# p-stop_03.net
KiCad netlist of a schematic drawn in EAGLE
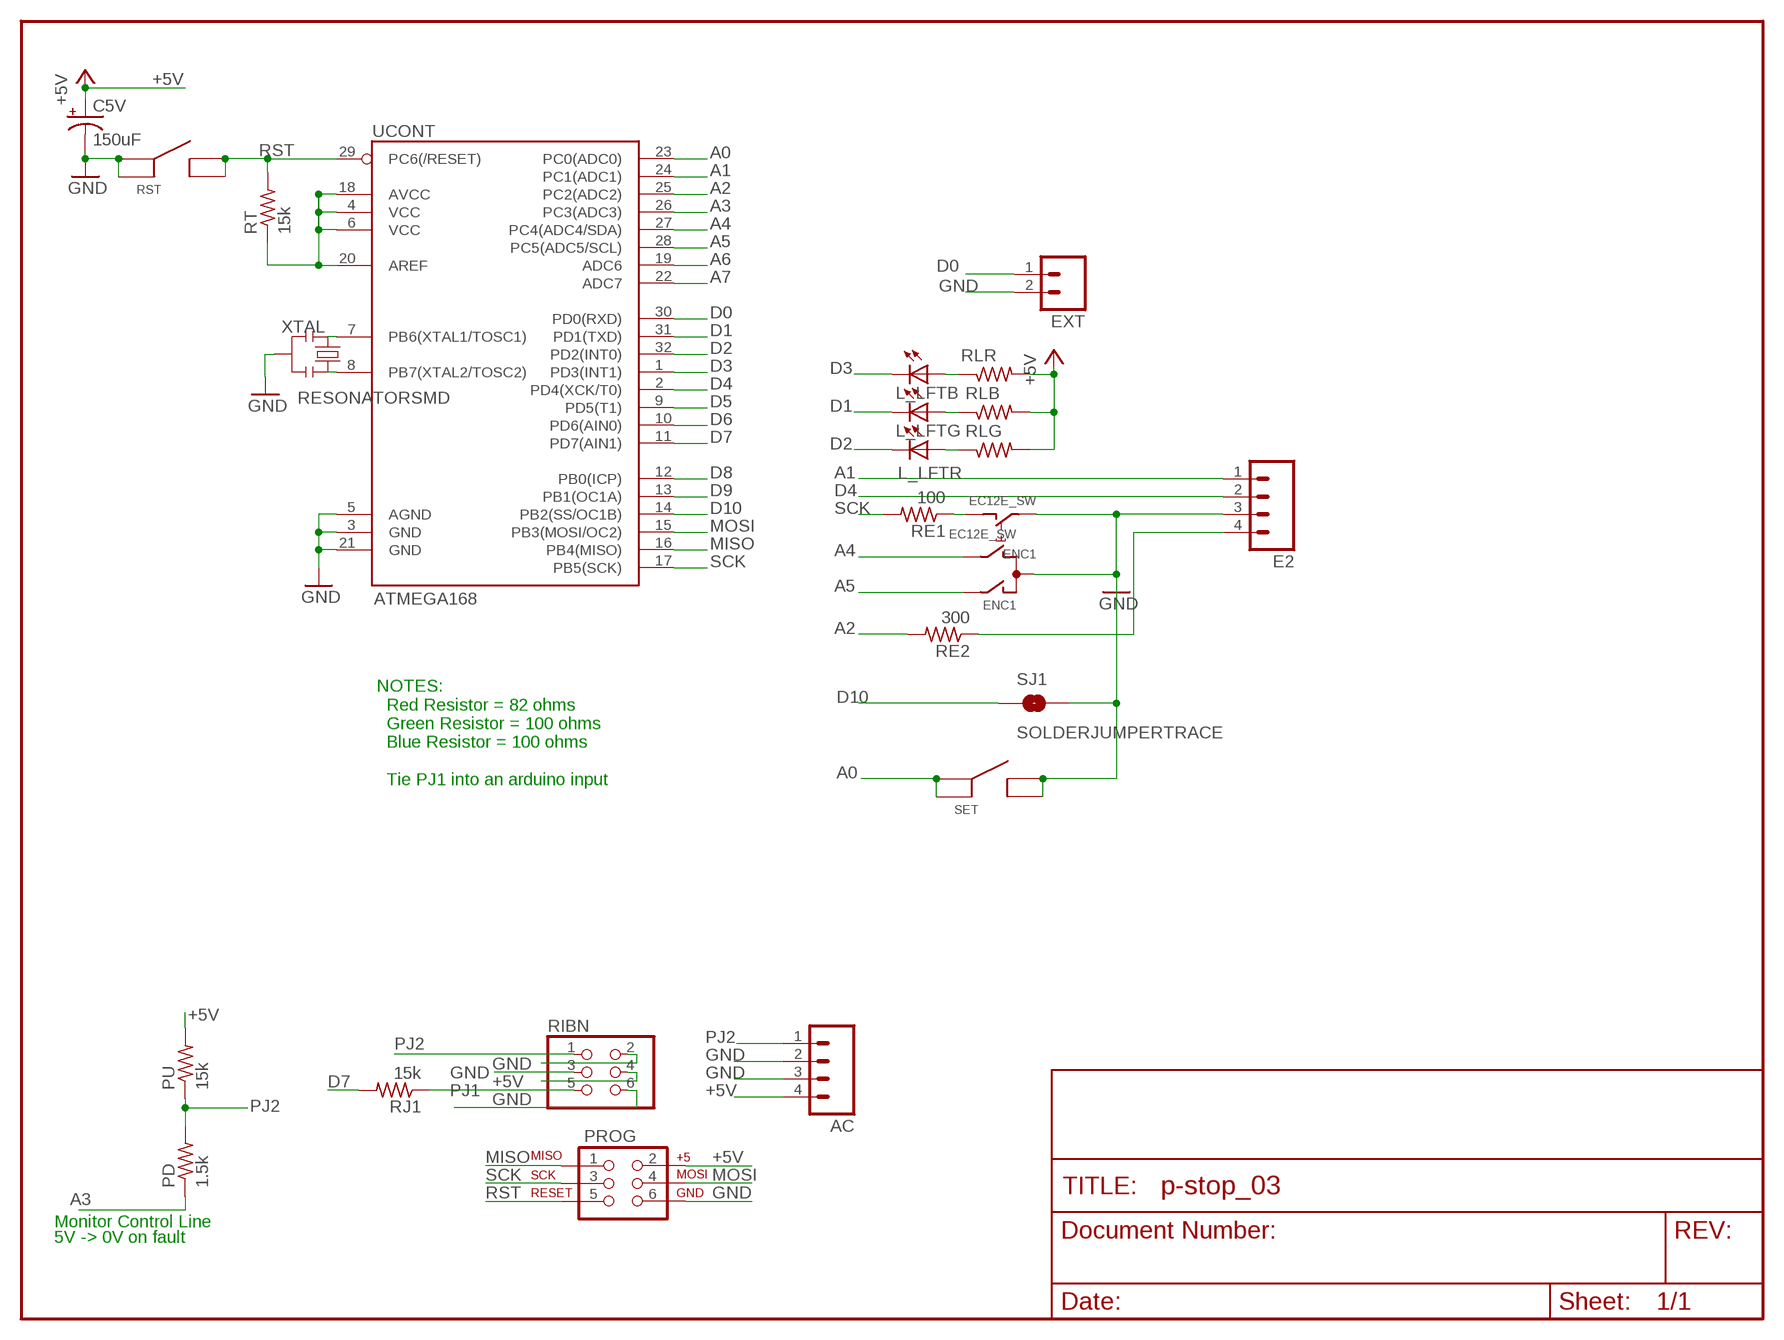
[diagram p0: schematic, sheet 1]

(export (version "E")
  (design (tool "Eeschema 10.0.6"))
  (components
    (comp (ref "AC")
      (value "M04PTH")
      (footprint "eagle-import:1X04")
      (libsource (lib "eagle-import") (part "M04PTH"))
    )
    (comp (ref "C5V")
      (value "150uF")
      (footprint "eagle-import:EIA3528")
      (libsource (lib "eagle-import") (part "CAP_POL3528"))
    )
    (comp (ref "E2")
      (value "M04PTH")
      (footprint "eagle-import:1X04")
      (libsource (lib "eagle-import") (part "M04PTH"))
    )
    (comp (ref "ENC1")
      (value "EC12E_SW")
      (footprint "eagle-import:ALPS_EC12E_SW")
      (fields (field (name "MPN") "EC12E2424407"))
      (libsource (lib "eagle-import") (part "EC12E_SW"))
    )
    (comp (ref "EXT")
      (value "M02PTH")
      (footprint "eagle-import:1X02")
      (libsource (lib "eagle-import") (part "M02PTH"))
    )
    (comp (ref "L_LFT")
      (value "GM5WA94310A")
      (footprint "eagle-import:GM5WA94310A")
      (libsource (lib "eagle-import") (part "GM5WA94310A"))
    )
    (comp (ref "PD")
      (value "1.5k")
      (footprint "eagle-import:MINI_MELF-0204R")
      (libsource (lib "eagle-import") (part "R-US_MELF0204R"))
    )
    (comp (ref "PROG")
      (value "AVR_SPI_PRG_6NS")
      (footprint "eagle-import:2X3-NS")
      (libsource (lib "eagle-import") (part "AVR_SPI_PRG_6NS"))
    )
    (comp (ref "PU")
      (value "15k")
      (footprint "eagle-import:MINI_MELF-0204R")
      (libsource (lib "eagle-import") (part "R-US_MELF0204R"))
    )
    (comp (ref "RE1")
      (value "100")
      (footprint "eagle-import:MINI_MELF-0204R")
      (libsource (lib "eagle-import") (part "R-US_MELF0204R"))
    )
    (comp (ref "RE2")
      (value "300")
      (footprint "eagle-import:MINI_MELF-0204R")
      (libsource (lib "eagle-import") (part "R-US_MELF0204R"))
    )
    (comp (ref "RIBN")
      (value "PINHD-2X3")
      (footprint "eagle-import:2X03")
      (libsource (lib "eagle-import") (part "PINHD-2X3"))
    )
    (comp (ref "RJ1")
      (value "15k")
      (footprint "eagle-import:MINI_MELF-0204R")
      (libsource (lib "eagle-import") (part "R-US_MELF0204R"))
    )
    (comp (ref "RLB")
      (value "100")
      (footprint "eagle-import:MINI_MELF-0204R")
      (libsource (lib "eagle-import") (part "R-US_MELF0204R"))
    )
    (comp (ref "RLG")
      (value "100")
      (footprint "eagle-import:MINI_MELF-0204R")
      (libsource (lib "eagle-import") (part "R-US_MELF0204R"))
    )
    (comp (ref "RLR")
      (value "100")
      (footprint "eagle-import:MINI_MELF-0204R")
      (libsource (lib "eagle-import") (part "R-US_MELF0204R"))
    )
    (comp (ref "RST")
      (value "6MM_TACT_SMD")
      (footprint "eagle-import:6MMSMDTACT")
      (libsource (lib "eagle-import") (part "6MM_TACT_SMD"))
    )
    (comp (ref "RT")
      (value "15k")
      (footprint "eagle-import:MINI_MELF-0204R")
      (libsource (lib "eagle-import") (part "R-US_MELF0204R"))
    )
    (comp (ref "SET")
      (value "6MM_TACT_SMD")
      (footprint "eagle-import:6MMSMDTACT")
      (libsource (lib "eagle-import") (part "6MM_TACT_SMD"))
    )
    (comp (ref "SJ1")
      (value "SOLDERJUMPERTRACE")
      (footprint "eagle-import:SJ_2S-TRACE")
      (libsource (lib "eagle-import") (part "SOLDERJUMPERTRACE"))
    )
    (comp (ref "UCONT")
      (value "ATMEGA168")
      (footprint "eagle-import:TQFP32-08")
      (libsource (lib "eagle-import") (part "ATMEGA168"))
    )
    (comp (ref "XTAL")
      (value "RESONATORSMD")
      (footprint "eagle-import:RESONATOR-SMD")
      (libsource (lib "eagle-import") (part "RESONATORSMD"))
    )
  )
  (nets
    (net (code "1") (name "+5V") (class "Default")
      (node (ref "AC") (pin "4") (pinfunction "4_4") (pintype "passive"))
      (node (ref "C5V") (pin "A") (pinfunction "+_A") (pintype "passive"))
      (node (ref "PROG") (pin "2") (pinfunction "2_2") (pintype "passive"))
      (node (ref "PU") (pin "2") (pinfunction "2_2") (pintype "passive"))
      (node (ref "RIBN") (pin "4") (pinfunction "4_4") (pintype "passive"))
      (node (ref "RLB") (pin "2") (pinfunction "2_2") (pintype "passive"))
      (node (ref "RLG") (pin "2") (pinfunction "2_2") (pintype "passive"))
      (node (ref "RLR") (pin "2") (pinfunction "2_2") (pintype "passive"))
      (node (ref "RT") (pin "1") (pinfunction "1_1") (pintype "passive"))
      (node (ref "UCONT") (pin "18") (pinfunction "AVCC_18") (pintype "bidirectional"))
      (node (ref "UCONT") (pin "20") (pinfunction "AREF_20") (pintype "bidirectional"))
      (node (ref "UCONT") (pin "4") (pinfunction "VCC_4") (pintype "bidirectional"))
      (node (ref "UCONT") (pin "6") (pinfunction "VCC_6") (pintype "bidirectional"))
    )
    (net (code "2") (name "/A0") (class "Default")
      (node (ref "SET") (pin "P1") (pinfunction "P1_P1") (pintype "bidirectional"))
      (node (ref "SET") (pin "P2") (pinfunction "P2_P2") (pintype "bidirectional"))
      (node (ref "UCONT") (pin "23") (pinfunction "PC0(ADC0)_23") (pintype "bidirectional"))
    )
    (net (code "3") (name "/A1") (class "Default")
      (node (ref "E2") (pin "1") (pinfunction "1_1") (pintype "passive"))
      (node (ref "UCONT") (pin "24") (pinfunction "PC1(ADC1)_24") (pintype "bidirectional"))
    )
    (net (code "4") (name "/A2") (class "Default")
      (node (ref "RE2") (pin "2") (pinfunction "2_2") (pintype "passive"))
      (node (ref "UCONT") (pin "25") (pinfunction "PC2(ADC2)_25") (pintype "bidirectional"))
    )
    (net (code "5") (name "/A3") (class "Default")
      (node (ref "PD") (pin "1") (pinfunction "1_1") (pintype "passive"))
      (node (ref "UCONT") (pin "26") (pinfunction "PC3(ADC3)_26") (pintype "bidirectional"))
    )
    (net (code "6") (name "/A4") (class "Default")
      (node (ref "ENC1") (pin "B") (pinfunction "B_B") (pintype "passive"))
      (node (ref "UCONT") (pin "27") (pinfunction "PC4(ADC4/SDA)_27") (pintype "bidirectional"))
    )
    (net (code "7") (name "/A5") (class "Default")
      (node (ref "ENC1") (pin "A") (pinfunction "A_A") (pintype "passive"))
      (node (ref "UCONT") (pin "28") (pinfunction "PC5(ADC5/SCL)_28") (pintype "bidirectional"))
    )
    (net (code "8") (name "/A6") (class "Default")
      (node (ref "UCONT") (pin "19") (pinfunction "ADC6_19") (pintype "bidirectional"))
    )
    (net (code "9") (name "/A7") (class "Default")
      (node (ref "UCONT") (pin "22") (pinfunction "ADC7_22") (pintype "bidirectional"))
    )
    (net (code "10") (name "/D0") (class "Default")
      (node (ref "EXT") (pin "1") (pinfunction "1_1") (pintype "passive"))
      (node (ref "UCONT") (pin "30") (pinfunction "PD0(RXD)_30") (pintype "bidirectional"))
    )
    (net (code "11") (name "/D1") (class "Default")
      (node (ref "L_LFT") (pin "4") (pinfunction "C_4") (pintype "passive"))
      (node (ref "UCONT") (pin "31") (pinfunction "PD1(TXD)_31") (pintype "bidirectional"))
    )
    (net (code "12") (name "/D2") (class "Default")
      (node (ref "L_LFT") (pin "5") (pinfunction "C_5") (pintype "passive"))
      (node (ref "UCONT") (pin "32") (pinfunction "PD2(INT0)_32") (pintype "bidirectional"))
    )
    (net (code "13") (name "/D3") (class "Default")
      (node (ref "L_LFT") (pin "6") (pinfunction "C_6") (pintype "passive"))
      (node (ref "UCONT") (pin "1") (pinfunction "PD3(INT1)_1") (pintype "bidirectional"))
    )
    (net (code "14") (name "/D4") (class "Default")
      (node (ref "E2") (pin "2") (pinfunction "2_2") (pintype "passive"))
      (node (ref "UCONT") (pin "2") (pinfunction "PD4(XCK/T0)_2") (pintype "bidirectional"))
    )
    (net (code "15") (name "/D5") (class "Default")
      (node (ref "UCONT") (pin "9") (pinfunction "PD5(T1)_9") (pintype "bidirectional"))
    )
    (net (code "16") (name "/D6") (class "Default")
      (node (ref "UCONT") (pin "10") (pinfunction "PD6(AIN0)_10") (pintype "bidirectional"))
    )
    (net (code "17") (name "/D7") (class "Default")
      (node (ref "RJ1") (pin "2") (pinfunction "2_2") (pintype "passive"))
      (node (ref "UCONT") (pin "11") (pinfunction "PD7(AIN1)_11") (pintype "bidirectional"))
    )
    (net (code "18") (name "/D8") (class "Default")
      (node (ref "UCONT") (pin "12") (pinfunction "PB0(ICP)_12") (pintype "bidirectional"))
    )
    (net (code "19") (name "/D9") (class "Default")
      (node (ref "UCONT") (pin "13") (pinfunction "PB1(OC1A)_13") (pintype "bidirectional"))
    )
    (net (code "20") (name "/D10") (class "Default")
      (node (ref "SJ1") (pin "1") (pinfunction "1_1") (pintype "passive"))
      (node (ref "UCONT") (pin "14") (pinfunction "PB2(SS/OC1B)_14") (pintype "bidirectional"))
    )
    (net (code "21") (name "/MISO") (class "Default")
      (node (ref "PROG") (pin "1") (pinfunction "1_1") (pintype "passive"))
      (node (ref "UCONT") (pin "16") (pinfunction "PB4(MISO)_16") (pintype "bidirectional"))
    )
    (net (code "22") (name "/MOSI") (class "Default")
      (node (ref "PROG") (pin "4") (pinfunction "4_4") (pintype "passive"))
      (node (ref "UCONT") (pin "15") (pinfunction "PB3(MOSI/OC2)_15") (pintype "bidirectional"))
    )
    (net (code "23") (name "/PJ1") (class "Default")
      (node (ref "RIBN") (pin "5") (pinfunction "5_5") (pintype "passive"))
      (node (ref "RJ1") (pin "1") (pinfunction "1_1") (pintype "passive"))
    )
    (net (code "24") (name "/PJ2") (class "Default")
      (node (ref "AC") (pin "1") (pinfunction "1_1") (pintype "passive"))
      (node (ref "PD") (pin "2") (pinfunction "2_2") (pintype "passive"))
      (node (ref "PU") (pin "1") (pinfunction "1_1") (pintype "passive"))
      (node (ref "RIBN") (pin "1") (pinfunction "1_1") (pintype "passive"))
    )
    (net (code "25") (name "/RST") (class "Default")
      (node (ref "PROG") (pin "5") (pinfunction "5_5") (pintype "passive"))
      (node (ref "RST") (pin "N1") (pinfunction "N1_N1") (pintype "bidirectional"))
      (node (ref "RST") (pin "N2") (pinfunction "N2_N2") (pintype "bidirectional"))
      (node (ref "RT") (pin "2") (pinfunction "2_2") (pintype "passive"))
      (node (ref "UCONT") (pin "29") (pinfunction "PC6(/RESET)_29") (pintype "bidirectional"))
    )
    (net (code "26") (name "/SCK") (class "Default")
      (node (ref "PROG") (pin "3") (pinfunction "3_3") (pintype "passive"))
      (node (ref "RE1") (pin "2") (pinfunction "2_2") (pintype "passive"))
      (node (ref "UCONT") (pin "17") (pinfunction "PB5(SCK)_17") (pintype "bidirectional"))
    )
    (net (code "27") (name "GND") (class "Default")
      (node (ref "AC") (pin "2") (pinfunction "2_2") (pintype "passive"))
      (node (ref "AC") (pin "3") (pinfunction "3_3") (pintype "passive"))
      (node (ref "C5V") (pin "C") (pinfunction "-_C") (pintype "passive"))
      (node (ref "E2") (pin "3") (pinfunction "3_3") (pintype "passive"))
      (node (ref "ENC1") (pin "C") (pinfunction "C_C") (pintype "passive"))
      (node (ref "ENC1") (pin "E") (pinfunction "2_E") (pintype "passive"))
      (node (ref "EXT") (pin "2") (pinfunction "2_2") (pintype "passive"))
      (node (ref "PROG") (pin "6") (pinfunction "6_6") (pintype "passive"))
      (node (ref "RIBN") (pin "2") (pinfunction "2_2") (pintype "passive"))
      (node (ref "RIBN") (pin "3") (pinfunction "3_3") (pintype "passive"))
      (node (ref "RIBN") (pin "6") (pinfunction "6_6") (pintype "passive"))
      (node (ref "RST") (pin "P1") (pinfunction "P1_P1") (pintype "bidirectional"))
      (node (ref "RST") (pin "P2") (pinfunction "P2_P2") (pintype "bidirectional"))
      (node (ref "SET") (pin "N1") (pinfunction "N1_N1") (pintype "bidirectional"))
      (node (ref "SET") (pin "N2") (pinfunction "N2_N2") (pintype "bidirectional"))
      (node (ref "SJ1") (pin "2") (pinfunction "2_2") (pintype "passive"))
      (node (ref "UCONT") (pin "21") (pinfunction "GND_21") (pintype "bidirectional"))
      (node (ref "UCONT") (pin "3") (pinfunction "GND_3") (pintype "bidirectional"))
      (node (ref "UCONT") (pin "5") (pinfunction "AGND_5") (pintype "bidirectional"))
      (node (ref "XTAL") (pin "2") (pinfunction "2_2") (pintype "passive"))
    )
    (net (code "28") (name "Net-(E2-Pad4)") (class "Default")
      (node (ref "E2") (pin "4") (pinfunction "4_4") (pintype "passive"))
      (node (ref "RE2") (pin "1") (pinfunction "1_1") (pintype "passive"))
    )
    (net (code "29") (name "Net-(ENC1B-1)") (class "Default")
      (node (ref "ENC1") (pin "D") (pinfunction "1_D") (pintype "passive"))
      (node (ref "RE1") (pin "1") (pinfunction "1_1") (pintype "passive"))
    )
    (net (code "30") (name "Net-(L_LFTA-A)") (class "Default")
      (node (ref "L_LFT") (pin "1") (pinfunction "A_1") (pintype "passive"))
      (node (ref "RLR") (pin "1") (pinfunction "1_1") (pintype "passive"))
    )
    (net (code "31") (name "Net-(L_LFTB-A)") (class "Default")
      (node (ref "L_LFT") (pin "3") (pinfunction "A_3") (pintype "passive"))
      (node (ref "RLB") (pin "1") (pinfunction "1_1") (pintype "passive"))
    )
    (net (code "32") (name "Net-(L_LFTC-A)") (class "Default")
      (node (ref "L_LFT") (pin "2") (pinfunction "A_2") (pintype "passive"))
      (node (ref "RLG") (pin "1") (pinfunction "1_1") (pintype "passive"))
    )
    (net (code "33") (name "Net-(UCONT-PB6(XTAL1{slash}TOSC1))") (class "Default")
      (node (ref "UCONT") (pin "7") (pinfunction "PB6(XTAL1/TOSC1)_7") (pintype "bidirectional"))
      (node (ref "XTAL") (pin "1") (pinfunction "1_1") (pintype "passive"))
    )
    (net (code "34") (name "Net-(UCONT-PB7(XTAL2{slash}TOSC2))") (class "Default")
      (node (ref "UCONT") (pin "8") (pinfunction "PB7(XTAL2/TOSC2)_8") (pintype "bidirectional"))
      (node (ref "XTAL") (pin "3") (pinfunction "3_3") (pintype "passive"))
    )
  )
)
